# MainBoard_2020-05-08_18-35-21.net
KiCad netlist of a schematic drawn in EasyEDA
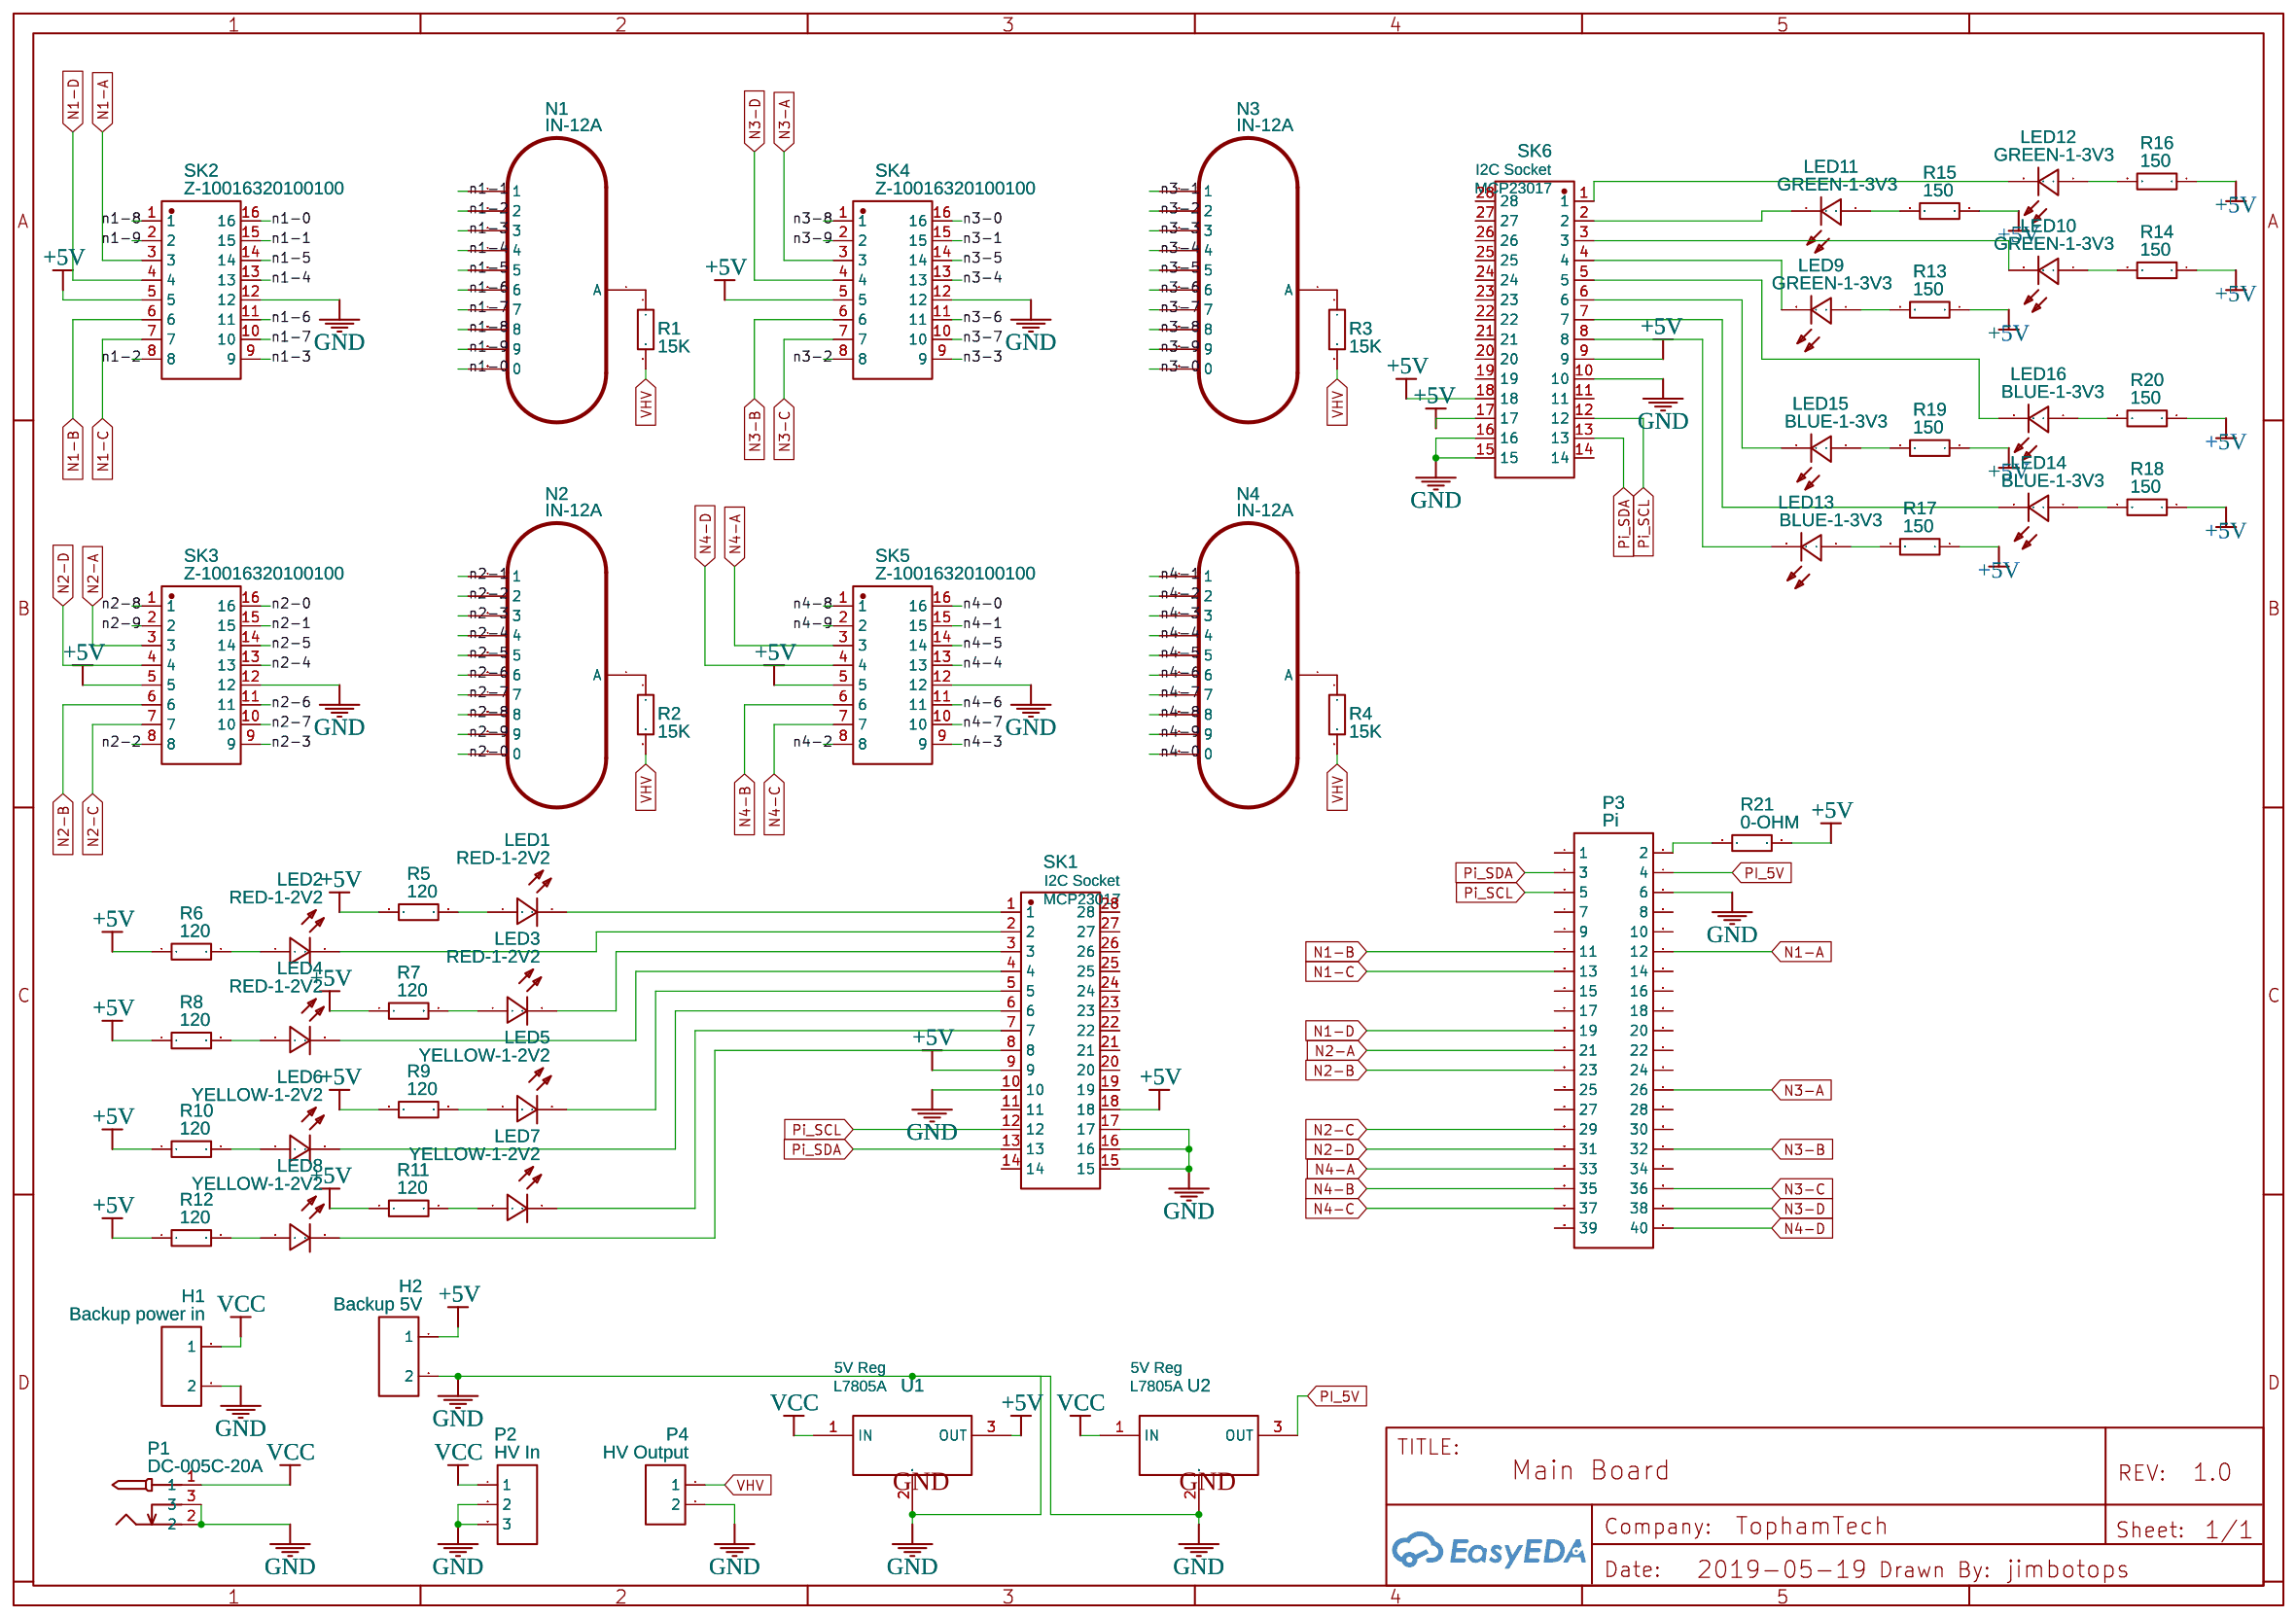
[diagram p0: schematic sheet]

(export (version "E")
  (design (tool "Eeschema 10.0.6"))
  (components
    (comp (ref "H1")
      (value "Backup power in")
      (fields (field (name "BOM_Manufacturer Part") "826629-2") (field (name "BOM_Supplier Part") "C86471"))
      (libsource (lib "") (part "Unknown_90_685"))
    )
    (comp (ref "H2")
      (value "Backup 5V")
      (fields (field (name "BOM_Manufacturer Part") "826629-2") (field (name "BOM_Supplier Part") "C86471"))
      (libsource (lib "") (part "Unknown_200_680"))
    )
    (comp (ref "LED1")
      (value "RED-1-2V2")
      (fields
        (field (name "BOM_Manufacturer Part") "11-21/GPC-AM2P1/2T")
        (field (name "BOM_Supplier Part") "C264329")
      )
      (libsource (lib "") (part "Unknown_260_455"))
    )
    (comp (ref "LED2")
      (value "RED-1-2V2")
      (fields
        (field (name "BOM_Manufacturer Part") "11-21/GPC-AM2P1/2T")
        (field (name "BOM_Supplier Part") "C264329")
      )
      (libsource (lib "") (part "Unknown_145_475"))
    )
    (comp (ref "LED3")
      (value "RED-1-2V2")
      (fields
        (field (name "BOM_Manufacturer Part") "11-21/GPC-AM2P1/2T")
        (field (name "BOM_Supplier Part") "C264329")
      )
      (libsource (lib "") (part "Unknown_255_505"))
    )
    (comp (ref "LED4")
      (value "RED-1-2V2")
      (fields
        (field (name "BOM_Manufacturer Part") "11-21/GPC-AM2P1/2T")
        (field (name "BOM_Supplier Part") "C264329")
      )
      (libsource (lib "") (part "Unknown_145_520"))
    )
    (comp (ref "LED5")
      (value "YELLOW-1-2V2")
      (fields
        (field (name "BOM_Manufacturer Part") "11-21/GPC-AM2P1/2T")
        (field (name "BOM_Supplier Part") "C264329")
      )
      (libsource (lib "") (part "Unknown_260_555"))
    )
    (comp (ref "LED6")
      (value "YELLOW-1-2V2")
      (fields
        (field (name "BOM_Manufacturer Part") "11-21/GPC-AM2P1/2T")
        (field (name "BOM_Supplier Part") "C264329")
      )
      (libsource (lib "") (part "Unknown_145_575"))
    )
    (comp (ref "LED7")
      (value "YELLOW-1-2V2")
      (fields
        (field (name "BOM_Manufacturer Part") "11-21/GPC-AM2P1/2T")
        (field (name "BOM_Supplier Part") "C264329")
      )
      (libsource (lib "") (part "Unknown_255_605"))
    )
    (comp (ref "LED8")
      (value "YELLOW-1-2V2")
      (fields
        (field (name "BOM_Manufacturer Part") "11-21/GPC-AM2P1/2T")
        (field (name "BOM_Supplier Part") "C264329")
      )
      (libsource (lib "") (part "Unknown_145_620"))
    )
    (comp (ref "LED9")
      (value "GREEN-1-3V3")
      (fields
        (field (name "BOM_Manufacturer Part") "11-21/GPC-AM2P1/2T")
        (field (name "BOM_Supplier Part") "C264329")
      )
      (libsource (lib "") (part "Unknown_915_150"))
    )
    (comp (ref "LED10")
      (value "GREEN-1-3V3")
      (fields
        (field (name "BOM_Manufacturer Part") "11-21/GPC-AM2P1/2T")
        (field (name "BOM_Supplier Part") "C264329")
      )
      (libsource (lib "") (part "Unknown_1030_130"))
    )
    (comp (ref "LED11")
      (value "GREEN-1-3V3")
      (fields
        (field (name "BOM_Manufacturer Part") "11-21/GPC-AM2P1/2T")
        (field (name "BOM_Supplier Part") "C264329")
      )
      (libsource (lib "") (part "Unknown_920_100"))
    )
    (comp (ref "LED12")
      (value "GREEN-1-3V3")
      (fields
        (field (name "BOM_Manufacturer Part") "11-21/GPC-AM2P1/2T")
        (field (name "BOM_Supplier Part") "C264329")
      )
      (libsource (lib "") (part "Unknown_1030_85"))
    )
    (comp (ref "LED13")
      (value "BLUE-1-3V3")
      (fields
        (field (name "BOM_Manufacturer Part") "11-21/GPC-AM2P1/2T")
        (field (name "BOM_Supplier Part") "C264329")
      )
      (libsource (lib "") (part "Unknown_910_270"))
    )
    (comp (ref "LED14")
      (value "BLUE-1-3V3")
      (fields
        (field (name "BOM_Manufacturer Part") "11-21/GPC-AM2P1/2T")
        (field (name "BOM_Supplier Part") "C264329")
      )
      (libsource (lib "") (part "Unknown_1025_250"))
    )
    (comp (ref "LED15")
      (value "BLUE-1-3V3")
      (fields
        (field (name "BOM_Manufacturer Part") "11-21/GPC-AM2P1/2T")
        (field (name "BOM_Supplier Part") "C264329")
      )
      (libsource (lib "") (part "Unknown_915_220"))
    )
    (comp (ref "LED16")
      (value "BLUE-1-3V3")
      (fields
        (field (name "BOM_Manufacturer Part") "11-21/GPC-AM2P1/2T")
        (field (name "BOM_Supplier Part") "C264329")
      )
      (libsource (lib "") (part "Unknown_1025_205"))
    )
    (comp (ref "N1")
      (value "IN-12A")
      (fields (field (name "BOM_Manufacturer Part") "?"))
      (libsource (lib "") (part "Unknown_275_135"))
    )
    (comp (ref "N2")
      (value "IN-12A")
      (fields (field (name "BOM_Manufacturer Part") "?"))
      (libsource (lib "") (part "Unknown_275_330"))
    )
    (comp (ref "N3")
      (value "IN-12A")
      (fields (field (name "BOM_Manufacturer Part") "?"))
      (libsource (lib "") (part "Unknown_625_135"))
    )
    (comp (ref "N4")
      (value "IN-12A")
      (fields (field (name "BOM_Manufacturer Part") "?"))
      (libsource (lib "") (part "Unknown_625_330"))
    )
    (comp (ref "P1")
      (value "DC-005C-20A")
      (fields (field (name "BOM_Supplier Part") "C84007"))
      (libsource (lib "") (part "Unknown_75_755"))
    )
    (comp (ref "P2")
      (value "HV In")
      (fields
        (field (name "BOM_Manufacturer Part") "Header-Female-2.54_1x3")
        (field (name "BOM_Supplier Part") "C146243")
      )
      (libsource (lib "") (part "Unknown_250_755"))
    )
    (comp (ref "P3")
      (value "Pi")
      (fields
        (field (name "BOM_Manufacturer Part") "2.54mm 2*20PFemale header")
        (field (name "BOM_Supplier Part") "C50982")
      )
      (libsource (lib "") (part "Unknown_810_525"))
    )
    (comp (ref "P4")
      (value "HV Output")
      (fields
        (field (name "BOM_Manufacturer Part") "2.54-1*2PFemale")
        (field (name "BOM_Supplier Part") "C49661")
      )
      (libsource (lib "") (part "Unknown_335_750"))
    )
    (comp (ref "R1")
      (value "15K")
      (fields
        (field (name "BOM_Manufacturer Part") "2010W2J0153T4S")
        (field (name "BOM_Supplier Part") "C20362")
      )
      (libsource (lib "") (part "2010W2J0153T4S"))
    )
    (comp (ref "R2")
      (value "15K")
      (fields
        (field (name "BOM_Manufacturer Part") "2010W2J0153T4S")
        (field (name "BOM_Supplier Part") "C20362")
      )
      (libsource (lib "") (part "2010W2J0153T4S"))
    )
    (comp (ref "R3")
      (value "15K")
      (fields
        (field (name "BOM_Manufacturer Part") "2010W2J0153T4S")
        (field (name "BOM_Supplier Part") "C20362")
      )
      (libsource (lib "") (part "2010W2J0153T4S"))
    )
    (comp (ref "R4")
      (value "15K")
      (fields
        (field (name "BOM_Manufacturer Part") "2010W2J0153T4S")
        (field (name "BOM_Supplier Part") "C20362")
      )
      (libsource (lib "") (part "2010W2J0153T4S"))
    )
    (comp (ref "R5")
      (value "120")
      (fields
        (field (name "BOM_Manufacturer Part") "1206W4F1200T5E")
        (field (name "BOM_Supplier Part") "C14661")
      )
      (libsource (lib "") (part "1206W4F1200T5E_1"))
    )
    (comp (ref "R6")
      (value "120")
      (fields
        (field (name "BOM_Manufacturer Part") "1206W4F1200T5E")
        (field (name "BOM_Supplier Part") "C14661")
      )
      (libsource (lib "") (part "1206W4F1200T5E_1"))
    )
    (comp (ref "R7")
      (value "120")
      (fields
        (field (name "BOM_Manufacturer Part") "1206W4F1200T5E")
        (field (name "BOM_Supplier Part") "C14661")
      )
      (libsource (lib "") (part "1206W4F1200T5E_1"))
    )
    (comp (ref "R8")
      (value "120")
      (fields
        (field (name "BOM_Manufacturer Part") "1206W4F1200T5E")
        (field (name "BOM_Supplier Part") "C14661")
      )
      (libsource (lib "") (part "1206W4F1200T5E_1"))
    )
    (comp (ref "R9")
      (value "120")
      (fields
        (field (name "BOM_Manufacturer Part") "1206W4F1200T5E")
        (field (name "BOM_Supplier Part") "C14661")
      )
      (libsource (lib "") (part "1206W4F1200T5E_1"))
    )
    (comp (ref "R10")
      (value "120")
      (fields
        (field (name "BOM_Manufacturer Part") "1206W4F1200T5E")
        (field (name "BOM_Supplier Part") "C14661")
      )
      (libsource (lib "") (part "1206W4F1200T5E_1"))
    )
    (comp (ref "R11")
      (value "120")
      (fields
        (field (name "BOM_Manufacturer Part") "1206W4F1200T5E")
        (field (name "BOM_Supplier Part") "C14661")
      )
      (libsource (lib "") (part "1206W4F1200T5E_1"))
    )
    (comp (ref "R12")
      (value "120")
      (fields
        (field (name "BOM_Manufacturer Part") "1206W4F1200T5E")
        (field (name "BOM_Supplier Part") "C14661")
      )
      (libsource (lib "") (part "1206W4F1200T5E_1"))
    )
    (comp (ref "R13")
      (value "150")
      (fields
        (field (name "BOM_Manufacturer Part") "1206W4F1200T5E")
        (field (name "BOM_Supplier Part") "C14661")
      )
      (libsource (lib "") (part "1206W4F1200T5E"))
    )
    (comp (ref "R14")
      (value "150")
      (fields
        (field (name "BOM_Manufacturer Part") "1206W4F1200T5E")
        (field (name "BOM_Supplier Part") "C14661")
      )
      (libsource (lib "") (part "1206W4F1200T5E"))
    )
    (comp (ref "R15")
      (value "150")
      (fields
        (field (name "BOM_Manufacturer Part") "1206W4F1200T5E")
        (field (name "BOM_Supplier Part") "C14661")
      )
      (libsource (lib "") (part "1206W4F1200T5E"))
    )
    (comp (ref "R16")
      (value "150")
      (fields
        (field (name "BOM_Manufacturer Part") "1206W4F1200T5E")
        (field (name "BOM_Supplier Part") "C14661")
      )
      (libsource (lib "") (part "1206W4F1200T5E"))
    )
    (comp (ref "R17")
      (value "150")
      (fields
        (field (name "BOM_Manufacturer Part") "1206W4F1200T5E")
        (field (name "BOM_Supplier Part") "C14661")
      )
      (libsource (lib "") (part "1206W4F1200T5E"))
    )
    (comp (ref "R18")
      (value "150")
      (fields
        (field (name "BOM_Manufacturer Part") "1206W4F1200T5E")
        (field (name "BOM_Supplier Part") "C14661")
      )
      (libsource (lib "") (part "1206W4F1200T5E"))
    )
    (comp (ref "R19")
      (value "150")
      (fields
        (field (name "BOM_Manufacturer Part") "1206W4F1200T5E")
        (field (name "BOM_Supplier Part") "C14661")
      )
      (libsource (lib "") (part "1206W4F1200T5E"))
    )
    (comp (ref "R20")
      (value "150")
      (fields
        (field (name "BOM_Manufacturer Part") "1206W4F1200T5E")
        (field (name "BOM_Supplier Part") "C14661")
      )
      (libsource (lib "") (part "1206W4F1200T5E"))
    )
    (comp (ref "R21")
      (value "0-OHM")
      (fields
        (field (name "BOM_Manufacturer Part") "1206W4F3650T5E")
        (field (name "BOM_Supplier Part") "C172882")
      )
      (libsource (lib "") (part "1206W4F3650T5E"))
    )
    (comp (ref "SK1")
      (value "I2C Socket\\nMCP23017")
      (fields (field (name "BOM_Supplier Part") "C146582"))
      (libsource (lib "") (part "Unknown_530_520"))
    )
    (comp (ref "SK2")
      (value "Z-10016320100100")
      (fields (field (name "BOM_Supplier Part") "C157594"))
      (libsource (lib "") (part "Unknown_95_140"))
    )
    (comp (ref "SK3")
      (value "Z-10016320100100")
      (fields (field (name "BOM_Supplier Part") "C157594"))
      (libsource (lib "") (part "Unknown_95_335"))
    )
    (comp (ref "SK4")
      (value "Z-10016320100100")
      (fields (field (name "BOM_Supplier Part") "C157594"))
      (libsource (lib "") (part "Unknown_445_140"))
    )
    (comp (ref "SK5")
      (value "Z-10016320100100")
      (fields (field (name "BOM_Supplier Part") "C157594"))
      (libsource (lib "") (part "Unknown_445_335"))
    )
    (comp (ref "SK6")
      (value "I2C Socket\\nMCP23017")
      (fields (field (name "BOM_Supplier Part") "C146582"))
      (libsource (lib "") (part "Unknown_770_160"))
    )
    (comp (ref "U1")
      (value "5V Reg\\nL7805A")
      (fields
        (field (name "BOM_Manufacturer Part") "L7805ABD2T-TR")
        (field (name "BOM_Supplier Part") "C86206")
      )
      (libsource (lib "") (part "Unknown_455_735"))
    )
    (comp (ref "U2")
      (value "5V Reg\\nL7805A")
      (fields
        (field (name "BOM_Manufacturer Part") "L7805ABD2T-TR")
        (field (name "BOM_Supplier Part") "C86206")
      )
      (libsource (lib "") (part "Unknown_600_735"))
    )
  )
  (nets
    (net (code "1") (name "+5V") (class "Default")
      (node (ref "H2") (pin "1") (pinfunction "1_1") (pintype "unspecified"))
      (node (ref "R10") (pin "1") (pinfunction "1_1") (pintype "input"))
      (node (ref "R11") (pin "1") (pinfunction "1_1") (pintype "input"))
      (node (ref "R12") (pin "1") (pinfunction "1_1") (pintype "input"))
      (node (ref "R13") (pin "1") (pinfunction "1_1") (pintype "input"))
      (node (ref "R14") (pin "1") (pinfunction "1_1") (pintype "input"))
      (node (ref "R15") (pin "1") (pinfunction "1_1") (pintype "input"))
      (node (ref "R16") (pin "1") (pinfunction "1_1") (pintype "input"))
      (node (ref "R17") (pin "1") (pinfunction "1_1") (pintype "input"))
      (node (ref "R18") (pin "1") (pinfunction "1_1") (pintype "input"))
      (node (ref "R19") (pin "1") (pinfunction "1_1") (pintype "input"))
      (node (ref "R20") (pin "1") (pinfunction "1_1") (pintype "input"))
      (node (ref "R21") (pin "2") (pinfunction "2_2") (pintype "unspecified"))
      (node (ref "R5") (pin "1") (pinfunction "1_1") (pintype "input"))
      (node (ref "R6") (pin "1") (pinfunction "1_1") (pintype "input"))
      (node (ref "R7") (pin "1") (pinfunction "1_1") (pintype "input"))
      (node (ref "R8") (pin "1") (pinfunction "1_1") (pintype "input"))
      (node (ref "R9") (pin "1") (pinfunction "1_1") (pintype "input"))
      (node (ref "SK1") (pin "18") (pinfunction "18_18") (pintype "unspecified"))
      (node (ref "SK1") (pin "9") (pinfunction "9_9") (pintype "unspecified"))
      (node (ref "SK2") (pin "5") (pinfunction "5_5") (pintype "unspecified"))
      (node (ref "SK3") (pin "5") (pinfunction "5_5") (pintype "unspecified"))
      (node (ref "SK4") (pin "5") (pinfunction "5_5") (pintype "unspecified"))
      (node (ref "SK5") (pin "5") (pinfunction "5_5") (pintype "unspecified"))
      (node (ref "SK6") (pin "17") (pinfunction "17_17") (pintype "unspecified"))
      (node (ref "SK6") (pin "18") (pinfunction "18_18") (pintype "unspecified"))
      (node (ref "SK6") (pin "9") (pinfunction "9_9") (pintype "unspecified"))
      (node (ref "U1") (pin "3") (pinfunction "OUT_3") (pintype "passive"))
    )
    (net (code "2") (name "/n1-0") (class "Default")
      (node (ref "N1") (pin "0") (pinfunction "0_0") (pintype "unspecified"))
      (node (ref "SK2") (pin "16") (pinfunction "16_16") (pintype "unspecified"))
    )
    (net (code "3") (name "/n1-1") (class "Default")
      (node (ref "N1") (pin "1") (pinfunction "1_1") (pintype "unspecified"))
      (node (ref "SK2") (pin "15") (pinfunction "15_15") (pintype "unspecified"))
    )
    (net (code "4") (name "/n1-2") (class "Default")
      (node (ref "N1") (pin "2") (pinfunction "2_2") (pintype "unspecified"))
      (node (ref "SK2") (pin "8") (pinfunction "8_8") (pintype "unspecified"))
    )
    (net (code "5") (name "/n1-3") (class "Default")
      (node (ref "N1") (pin "3") (pinfunction "3_3") (pintype "unspecified"))
      (node (ref "SK2") (pin "9") (pinfunction "9_9") (pintype "unspecified"))
    )
    (net (code "6") (name "/n1-4") (class "Default")
      (node (ref "N1") (pin "4") (pinfunction "4_4") (pintype "unspecified"))
      (node (ref "SK2") (pin "13") (pinfunction "13_13") (pintype "unspecified"))
    )
    (net (code "7") (name "/n1-5") (class "Default")
      (node (ref "N1") (pin "5") (pinfunction "5_5") (pintype "unspecified"))
      (node (ref "SK2") (pin "14") (pinfunction "14_14") (pintype "unspecified"))
    )
    (net (code "8") (name "/n1-6") (class "Default")
      (node (ref "N1") (pin "6") (pinfunction "6_6") (pintype "unspecified"))
      (node (ref "SK2") (pin "11") (pinfunction "11_11") (pintype "unspecified"))
    )
    (net (code "9") (name "/n1-7") (class "Default")
      (node (ref "N1") (pin "7") (pinfunction "7_7") (pintype "unspecified"))
      (node (ref "SK2") (pin "10") (pinfunction "10_10") (pintype "unspecified"))
    )
    (net (code "10") (name "/n1-8") (class "Default")
      (node (ref "N1") (pin "8") (pinfunction "8_8") (pintype "unspecified"))
      (node (ref "SK2") (pin "1") (pinfunction "1_1") (pintype "unspecified"))
    )
    (net (code "11") (name "/n1-9") (class "Default")
      (node (ref "N1") (pin "9") (pinfunction "9_9") (pintype "unspecified"))
      (node (ref "SK2") (pin "2") (pinfunction "2_2") (pintype "unspecified"))
    )
    (net (code "12") (name "/n2-0") (class "Default")
      (node (ref "N2") (pin "0") (pinfunction "0_0") (pintype "unspecified"))
      (node (ref "SK3") (pin "16") (pinfunction "16_16") (pintype "unspecified"))
    )
    (net (code "13") (name "/n2-1") (class "Default")
      (node (ref "N2") (pin "1") (pinfunction "1_1") (pintype "unspecified"))
      (node (ref "SK3") (pin "15") (pinfunction "15_15") (pintype "unspecified"))
    )
    (net (code "14") (name "/n2-2") (class "Default")
      (node (ref "N2") (pin "2") (pinfunction "2_2") (pintype "unspecified"))
      (node (ref "SK3") (pin "8") (pinfunction "8_8") (pintype "unspecified"))
    )
    (net (code "15") (name "/n2-3") (class "Default")
      (node (ref "N2") (pin "3") (pinfunction "3_3") (pintype "unspecified"))
      (node (ref "SK3") (pin "9") (pinfunction "9_9") (pintype "unspecified"))
    )
    (net (code "16") (name "/n2-4") (class "Default")
      (node (ref "N2") (pin "4") (pinfunction "4_4") (pintype "unspecified"))
      (node (ref "SK3") (pin "13") (pinfunction "13_13") (pintype "unspecified"))
    )
    (net (code "17") (name "/n2-5") (class "Default")
      (node (ref "N2") (pin "5") (pinfunction "5_5") (pintype "unspecified"))
      (node (ref "SK3") (pin "14") (pinfunction "14_14") (pintype "unspecified"))
    )
    (net (code "18") (name "/n2-6") (class "Default")
      (node (ref "N2") (pin "6") (pinfunction "6_6") (pintype "unspecified"))
      (node (ref "SK3") (pin "11") (pinfunction "11_11") (pintype "unspecified"))
    )
    (net (code "19") (name "/n2-7") (class "Default")
      (node (ref "N2") (pin "7") (pinfunction "7_7") (pintype "unspecified"))
      (node (ref "SK3") (pin "10") (pinfunction "10_10") (pintype "unspecified"))
    )
    (net (code "20") (name "/n2-8") (class "Default")
      (node (ref "N2") (pin "8") (pinfunction "8_8") (pintype "unspecified"))
      (node (ref "SK3") (pin "1") (pinfunction "1_1") (pintype "unspecified"))
    )
    (net (code "21") (name "/n2-9") (class "Default")
      (node (ref "N2") (pin "9") (pinfunction "9_9") (pintype "unspecified"))
      (node (ref "SK3") (pin "2") (pinfunction "2_2") (pintype "unspecified"))
    )
    (net (code "22") (name "/n3-0") (class "Default")
      (node (ref "N3") (pin "0") (pinfunction "0_0") (pintype "unspecified"))
      (node (ref "SK4") (pin "16") (pinfunction "16_16") (pintype "unspecified"))
    )
    (net (code "23") (name "/n3-1") (class "Default")
      (node (ref "N3") (pin "1") (pinfunction "1_1") (pintype "unspecified"))
      (node (ref "SK4") (pin "15") (pinfunction "15_15") (pintype "unspecified"))
    )
    (net (code "24") (name "/n3-2") (class "Default")
      (node (ref "N3") (pin "2") (pinfunction "2_2") (pintype "unspecified"))
      (node (ref "SK4") (pin "8") (pinfunction "8_8") (pintype "unspecified"))
    )
    (net (code "25") (name "/n3-3") (class "Default")
      (node (ref "N3") (pin "3") (pinfunction "3_3") (pintype "unspecified"))
      (node (ref "SK4") (pin "9") (pinfunction "9_9") (pintype "unspecified"))
    )
    (net (code "26") (name "/n3-4") (class "Default")
      (node (ref "N3") (pin "4") (pinfunction "4_4") (pintype "unspecified"))
      (node (ref "SK4") (pin "13") (pinfunction "13_13") (pintype "unspecified"))
    )
    (net (code "27") (name "/n3-5") (class "Default")
      (node (ref "N3") (pin "5") (pinfunction "5_5") (pintype "unspecified"))
      (node (ref "SK4") (pin "14") (pinfunction "14_14") (pintype "unspecified"))
    )
    (net (code "28") (name "/n3-6") (class "Default")
      (node (ref "N3") (pin "6") (pinfunction "6_6") (pintype "unspecified"))
      (node (ref "SK4") (pin "11") (pinfunction "11_11") (pintype "unspecified"))
    )
    (net (code "29") (name "/n3-7") (class "Default")
      (node (ref "N3") (pin "7") (pinfunction "7_7") (pintype "unspecified"))
      (node (ref "SK4") (pin "10") (pinfunction "10_10") (pintype "unspecified"))
    )
    (net (code "30") (name "/n3-8") (class "Default")
      (node (ref "N3") (pin "8") (pinfunction "8_8") (pintype "unspecified"))
      (node (ref "SK4") (pin "1") (pinfunction "1_1") (pintype "unspecified"))
    )
    (net (code "31") (name "/n3-9") (class "Default")
      (node (ref "N3") (pin "9") (pinfunction "9_9") (pintype "unspecified"))
      (node (ref "SK4") (pin "2") (pinfunction "2_2") (pintype "unspecified"))
    )
    (net (code "32") (name "/n4-0") (class "Default")
      (node (ref "N4") (pin "0") (pinfunction "0_0") (pintype "unspecified"))
      (node (ref "SK5") (pin "16") (pinfunction "16_16") (pintype "unspecified"))
    )
    (net (code "33") (name "/n4-1") (class "Default")
      (node (ref "N4") (pin "1") (pinfunction "1_1") (pintype "unspecified"))
      (node (ref "SK5") (pin "15") (pinfunction "15_15") (pintype "unspecified"))
    )
    (net (code "34") (name "/n4-2") (class "Default")
      (node (ref "N4") (pin "2") (pinfunction "2_2") (pintype "unspecified"))
      (node (ref "SK5") (pin "8") (pinfunction "8_8") (pintype "unspecified"))
    )
    (net (code "35") (name "/n4-3") (class "Default")
      (node (ref "N4") (pin "3") (pinfunction "3_3") (pintype "unspecified"))
      (node (ref "SK5") (pin "9") (pinfunction "9_9") (pintype "unspecified"))
    )
    (net (code "36") (name "/n4-4") (class "Default")
      (node (ref "N4") (pin "4") (pinfunction "4_4") (pintype "unspecified"))
      (node (ref "SK5") (pin "13") (pinfunction "13_13") (pintype "unspecified"))
    )
    (net (code "37") (name "/n4-5") (class "Default")
      (node (ref "N4") (pin "5") (pinfunction "5_5") (pintype "unspecified"))
      (node (ref "SK5") (pin "14") (pinfunction "14_14") (pintype "unspecified"))
    )
    (net (code "38") (name "/n4-6") (class "Default")
      (node (ref "N4") (pin "6") (pinfunction "6_6") (pintype "unspecified"))
      (node (ref "SK5") (pin "11") (pinfunction "11_11") (pintype "unspecified"))
    )
    (net (code "39") (name "/n4-7") (class "Default")
      (node (ref "N4") (pin "7") (pinfunction "7_7") (pintype "unspecified"))
      (node (ref "SK5") (pin "10") (pinfunction "10_10") (pintype "unspecified"))
    )
    (net (code "40") (name "/n4-8") (class "Default")
      (node (ref "N4") (pin "8") (pinfunction "8_8") (pintype "unspecified"))
      (node (ref "SK5") (pin "1") (pinfunction "1_1") (pintype "unspecified"))
    )
    (net (code "41") (name "/n4-9") (class "Default")
      (node (ref "N4") (pin "9") (pinfunction "9_9") (pintype "unspecified"))
      (node (ref "SK5") (pin "2") (pinfunction "2_2") (pintype "unspecified"))
    )
    (net (code "42") (name "GND") (class "Default")
      (node (ref "H1") (pin "2") (pinfunction "2_2") (pintype "unspecified"))
      (node (ref "H2") (pin "2") (pinfunction "2_2") (pintype "unspecified"))
      (node (ref "P1") (pin "2") (pinfunction "2_2") (pintype "unspecified"))
      (node (ref "P1") (pin "3") (pinfunction "3_3") (pintype "unspecified"))
      (node (ref "P2") (pin "2") (pinfunction "2_2") (pintype "input"))
      (node (ref "P2") (pin "3") (pinfunction "3_3") (pintype "input"))
      (node (ref "P3") (pin "6") (pinfunction "6_6") (pintype "input"))
      (node (ref "P4") (pin "2") (pinfunction "2_2") (pintype "input"))
      (node (ref "SK1") (pin "10") (pinfunction "10_10") (pintype "unspecified"))
      (node (ref "SK1") (pin "15") (pinfunction "15_15") (pintype "unspecified"))
      (node (ref "SK1") (pin "16") (pinfunction "16_16") (pintype "unspecified"))
      (node (ref "SK1") (pin "17") (pinfunction "17_17") (pintype "unspecified"))
      (node (ref "SK2") (pin "12") (pinfunction "12_12") (pintype "unspecified"))
      (node (ref "SK3") (pin "12") (pinfunction "12_12") (pintype "unspecified"))
      (node (ref "SK4") (pin "12") (pinfunction "12_12") (pintype "unspecified"))
      (node (ref "SK5") (pin "12") (pinfunction "12_12") (pintype "unspecified"))
      (node (ref "SK6") (pin "10") (pinfunction "10_10") (pintype "unspecified"))
      (node (ref "SK6") (pin "15") (pinfunction "15_15") (pintype "unspecified"))
      (node (ref "SK6") (pin "16") (pinfunction "16_16") (pintype "unspecified"))
      (node (ref "U1") (pin "2") (pinfunction "GND_2") (pintype "passive"))
      (node (ref "U2") (pin "2") (pinfunction "GND_2") (pintype "passive"))
    )
    (net (code "43") (name "N1-A") (class "Default")
      (node (ref "P3") (pin "12") (pinfunction "12_12") (pintype "input"))
      (node (ref "SK2") (pin "3") (pinfunction "3_3") (pintype "unspecified"))
    )
    (net (code "44") (name "N1-B") (class "Default")
      (node (ref "P3") (pin "11") (pinfunction "11_11") (pintype "input"))
      (node (ref "SK2") (pin "6") (pinfunction "6_6") (pintype "unspecified"))
    )
    (net (code "45") (name "N1-C") (class "Default")
      (node (ref "P3") (pin "13") (pinfunction "13_13") (pintype "input"))
      (node (ref "SK2") (pin "7") (pinfunction "7_7") (pintype "unspecified"))
    )
    (net (code "46") (name "N1-D") (class "Default")
      (node (ref "P3") (pin "19") (pinfunction "19_19") (pintype "input"))
      (node (ref "SK2") (pin "4") (pinfunction "4_4") (pintype "unspecified"))
    )
    (net (code "47") (name "N2-A") (class "Default")
      (node (ref "P3") (pin "21") (pinfunction "21_21") (pintype "input"))
      (node (ref "SK3") (pin "3") (pinfunction "3_3") (pintype "unspecified"))
    )
    (net (code "48") (name "N2-B") (class "Default")
      (node (ref "P3") (pin "23") (pinfunction "23_23") (pintype "input"))
      (node (ref "SK3") (pin "6") (pinfunction "6_6") (pintype "unspecified"))
    )
    (net (code "49") (name "N2-C") (class "Default")
      (node (ref "P3") (pin "29") (pinfunction "29_29") (pintype "input"))
      (node (ref "SK3") (pin "7") (pinfunction "7_7") (pintype "unspecified"))
    )
    (net (code "50") (name "N2-D") (class "Default")
      (node (ref "P3") (pin "31") (pinfunction "31_31") (pintype "input"))
      (node (ref "SK3") (pin "4") (pinfunction "4_4") (pintype "unspecified"))
    )
    (net (code "51") (name "N3-A") (class "Default")
      (node (ref "P3") (pin "26") (pinfunction "26_26") (pintype "input"))
      (node (ref "SK4") (pin "3") (pinfunction "3_3") (pintype "unspecified"))
    )
    (net (code "52") (name "N3-B") (class "Default")
      (node (ref "P3") (pin "32") (pinfunction "32_32") (pintype "input"))
      (node (ref "SK4") (pin "6") (pinfunction "6_6") (pintype "unspecified"))
    )
    (net (code "53") (name "N3-C") (class "Default")
      (node (ref "P3") (pin "36") (pinfunction "36_36") (pintype "input"))
      (node (ref "SK4") (pin "7") (pinfunction "7_7") (pintype "unspecified"))
    )
    (net (code "54") (name "N3-D") (class "Default")
      (node (ref "P3") (pin "38") (pinfunction "38_38") (pintype "input"))
      (node (ref "SK4") (pin "4") (pinfunction "4_4") (pintype "unspecified"))
    )
    (net (code "55") (name "N4-A") (class "Default")
      (node (ref "P3") (pin "33") (pinfunction "33_33") (pintype "input"))
      (node (ref "SK5") (pin "3") (pinfunction "3_3") (pintype "unspecified"))
    )
    (net (code "56") (name "N4-B") (class "Default")
      (node (ref "P3") (pin "35") (pinfunction "35_35") (pintype "input"))
      (node (ref "SK5") (pin "6") (pinfunction "6_6") (pintype "unspecified"))
    )
    (net (code "57") (name "N4-C") (class "Default")
      (node (ref "P3") (pin "37") (pinfunction "37_37") (pintype "input"))
      (node (ref "SK5") (pin "7") (pinfunction "7_7") (pintype "unspecified"))
    )
    (net (code "58") (name "N4-D") (class "Default")
      (node (ref "P3") (pin "40") (pinfunction "40_40") (pintype "input"))
      (node (ref "SK5") (pin "4") (pinfunction "4_4") (pintype "unspecified"))
    )
    (net (code "59") (name "Net-(LED1-A)") (class "Default")
      (node (ref "LED1") (pin "1") (pinfunction "A_1") (pintype "unspecified"))
      (node (ref "R5") (pin "2") (pinfunction "2_2") (pintype "input"))
    )
    (net (code "60") (name "Net-(LED1-K)") (class "Default")
      (node (ref "LED1") (pin "2") (pinfunction "K_2") (pintype "unspecified"))
      (node (ref "SK1") (pin "1") (pinfunction "1_1") (pintype "unspecified"))
    )
    (net (code "61") (name "Net-(LED2-A)") (class "Default")
      (node (ref "LED2") (pin "1") (pinfunction "A_1") (pintype "unspecified"))
      (node (ref "R6") (pin "2") (pinfunction "2_2") (pintype "input"))
    )
    (net (code "62") (name "Net-(LED2-K)") (class "Default")
      (node (ref "LED2") (pin "2") (pinfunction "K_2") (pintype "unspecified"))
      (node (ref "SK1") (pin "2") (pinfunction "2_2") (pintype "unspecified"))
    )
    (net (code "63") (name "Net-(LED3-A)") (class "Default")
      (node (ref "LED3") (pin "1") (pinfunction "A_1") (pintype "unspecified"))
      (node (ref "R7") (pin "2") (pinfunction "2_2") (pintype "input"))
    )
    (net (code "64") (name "Net-(LED3-K)") (class "Default")
      (node (ref "LED3") (pin "2") (pinfunction "K_2") (pintype "unspecified"))
      (node (ref "SK1") (pin "3") (pinfunction "3_3") (pintype "unspecified"))
    )
    (net (code "65") (name "Net-(LED4-A)") (class "Default")
      (node (ref "LED4") (pin "1") (pinfunction "A_1") (pintype "unspecified"))
      (node (ref "R8") (pin "2") (pinfunction "2_2") (pintype "input"))
    )
    (net (code "66") (name "Net-(LED4-K)") (class "Default")
      (node (ref "LED4") (pin "2") (pinfunction "K_2") (pintype "unspecified"))
      (node (ref "SK1") (pin "4") (pinfunction "4_4") (pintype "unspecified"))
    )
    (net (code "67") (name "Net-(LED5-A)") (class "Default")
      (node (ref "LED5") (pin "1") (pinfunction "A_1") (pintype "unspecified"))
      (node (ref "R9") (pin "2") (pinfunction "2_2") (pintype "input"))
    )
    (net (code "68") (name "Net-(LED5-K)") (class "Default")
      (node (ref "LED5") (pin "2") (pinfunction "K_2") (pintype "unspecified"))
      (node (ref "SK1") (pin "5") (pinfunction "5_5") (pintype "unspecified"))
    )
    (net (code "69") (name "Net-(LED6-A)") (class "Default")
      (node (ref "LED6") (pin "1") (pinfunction "A_1") (pintype "unspecified"))
      (node (ref "R10") (pin "2") (pinfunction "2_2") (pintype "input"))
    )
    (net (code "70") (name "Net-(LED6-K)") (class "Default")
      (node (ref "LED6") (pin "2") (pinfunction "K_2") (pintype "unspecified"))
      (node (ref "SK1") (pin "6") (pinfunction "6_6") (pintype "unspecified"))
    )
    (net (code "71") (name "Net-(LED7-A)") (class "Default")
      (node (ref "LED7") (pin "1") (pinfunction "A_1") (pintype "unspecified"))
      (node (ref "R11") (pin "2") (pinfunction "2_2") (pintype "input"))
    )
    (net (code "72") (name "Net-(LED7-K)") (class "Default")
      (node (ref "LED7") (pin "2") (pinfunction "K_2") (pintype "unspecified"))
      (node (ref "SK1") (pin "7") (pinfunction "7_7") (pintype "unspecified"))
    )
    (net (code "73") (name "Net-(LED8-A)") (class "Default")
      (node (ref "LED8") (pin "1") (pinfunction "A_1") (pintype "unspecified"))
      (node (ref "R12") (pin "2") (pinfunction "2_2") (pintype "input"))
    )
    (net (code "74") (name "Net-(LED8-K)") (class "Default")
      (node (ref "LED8") (pin "2") (pinfunction "K_2") (pintype "unspecified"))
      (node (ref "SK1") (pin "8") (pinfunction "8_8") (pintype "unspecified"))
    )
    (net (code "75") (name "Net-(LED9-A)") (class "Default")
      (node (ref "LED9") (pin "1") (pinfunction "A_1") (pintype "unspecified"))
      (node (ref "R13") (pin "2") (pinfunction "2_2") (pintype "input"))
    )
    (net (code "76") (name "Net-(LED9-K)") (class "Default")
      (node (ref "LED9") (pin "2") (pinfunction "K_2") (pintype "unspecified"))
      (node (ref "SK6") (pin "4") (pinfunction "4_4") (pintype "unspecified"))
    )
    (net (code "77") (name "Net-(LED10-A)") (class "Default")
      (node (ref "LED10") (pin "1") (pinfunction "A_1") (pintype "unspecified"))
      (node (ref "R14") (pin "2") (pinfunction "2_2") (pintype "input"))
    )
    (net (code "78") (name "Net-(LED10-K)") (class "Default")
      (node (ref "LED10") (pin "2") (pinfunction "K_2") (pintype "unspecified"))
      (node (ref "SK6") (pin "3") (pinfunction "3_3") (pintype "unspecified"))
    )
    (net (code "79") (name "Net-(LED11-A)") (class "Default")
      (node (ref "LED11") (pin "1") (pinfunction "A_1") (pintype "unspecified"))
      (node (ref "R15") (pin "2") (pinfunction "2_2") (pintype "input"))
    )
    (net (code "80") (name "Net-(LED11-K)") (class "Default")
      (node (ref "LED11") (pin "2") (pinfunction "K_2") (pintype "unspecified"))
      (node (ref "SK6") (pin "2") (pinfunction "2_2") (pintype "unspecified"))
    )
    (net (code "81") (name "Net-(LED12-A)") (class "Default")
      (node (ref "LED12") (pin "1") (pinfunction "A_1") (pintype "unspecified"))
      (node (ref "R16") (pin "2") (pinfunction "2_2") (pintype "input"))
    )
    (net (code "82") (name "Net-(LED12-K)") (class "Default")
      (node (ref "LED12") (pin "2") (pinfunction "K_2") (pintype "unspecified"))
      (node (ref "SK6") (pin "1") (pinfunction "1_1") (pintype "unspecified"))
    )
    (net (code "83") (name "Net-(LED13-A)") (class "Default")
      (node (ref "LED13") (pin "1") (pinfunction "A_1") (pintype "unspecified"))
      (node (ref "R17") (pin "2") (pinfunction "2_2") (pintype "input"))
    )
    (net (code "84") (name "Net-(LED13-K)") (class "Default")
      (node (ref "LED13") (pin "2") (pinfunction "K_2") (pintype "unspecified"))
      (node (ref "SK6") (pin "8") (pinfunction "8_8") (pintype "unspecified"))
    )
    (net (code "85") (name "Net-(LED14-A)") (class "Default")
      (node (ref "LED14") (pin "1") (pinfunction "A_1") (pintype "unspecified"))
      (node (ref "R18") (pin "2") (pinfunction "2_2") (pintype "input"))
    )
    (net (code "86") (name "Net-(LED14-K)") (class "Default")
      (node (ref "LED14") (pin "2") (pinfunction "K_2") (pintype "unspecified"))
      (node (ref "SK6") (pin "7") (pinfunction "7_7") (pintype "unspecified"))
    )
    (net (code "87") (name "Net-(LED15-A)") (class "Default")
      (node (ref "LED15") (pin "1") (pinfunction "A_1") (pintype "unspecified"))
      (node (ref "R19") (pin "2") (pinfunction "2_2") (pintype "input"))
    )
    (net (code "88") (name "Net-(LED15-K)") (class "Default")
      (node (ref "LED15") (pin "2") (pinfunction "K_2") (pintype "unspecified"))
      (node (ref "SK6") (pin "6") (pinfunction "6_6") (pintype "unspecified"))
    )
    (net (code "89") (name "Net-(LED16-A)") (class "Default")
      (node (ref "LED16") (pin "1") (pinfunction "A_1") (pintype "unspecified"))
      (node (ref "R20") (pin "2") (pinfunction "2_2") (pintype "input"))
    )
    (net (code "90") (name "Net-(LED16-K)") (class "Default")
      (node (ref "LED16") (pin "2") (pinfunction "K_2") (pintype "unspecified"))
      (node (ref "SK6") (pin "5") (pinfunction "5_5") (pintype "unspecified"))
    )
    (net (code "91") (name "Net-(N1-PadA)") (class "Default")
      (node (ref "N1") (pin "A") (pinfunction "A_A") (pintype "unspecified"))
      (node (ref "R1") (pin "1") (pinfunction "1_1") (pintype "input"))
    )
    (net (code "92") (name "Net-(N2-PadA)") (class "Default")
      (node (ref "N2") (pin "A") (pinfunction "A_A") (pintype "unspecified"))
      (node (ref "R2") (pin "1") (pinfunction "1_1") (pintype "input"))
    )
    (net (code "93") (name "Net-(N3-PadA)") (class "Default")
      (node (ref "N3") (pin "A") (pinfunction "A_A") (pintype "unspecified"))
      (node (ref "R3") (pin "1") (pinfunction "1_1") (pintype "input"))
    )
    (net (code "94") (name "Net-(N4-PadA)") (class "Default")
      (node (ref "N4") (pin "A") (pinfunction "A_A") (pintype "unspecified"))
      (node (ref "R4") (pin "1") (pinfunction "1_1") (pintype "input"))
    )
    (net (code "95") (name "Net-(P3-Pad2)") (class "Default")
      (node (ref "P3") (pin "2") (pinfunction "2_2") (pintype "input"))
      (node (ref "R21") (pin "1") (pinfunction "1_1") (pintype "unspecified"))
    )
    (net (code "96") (name "PI_5V") (class "Default")
      (node (ref "P3") (pin "4") (pinfunction "4_4") (pintype "input"))
      (node (ref "U2") (pin "3") (pinfunction "OUT_3") (pintype "passive"))
    )
    (net (code "97") (name "Pi_SCL") (class "Default")
      (node (ref "P3") (pin "5") (pinfunction "5_5") (pintype "input"))
      (node (ref "SK1") (pin "12") (pinfunction "12_12") (pintype "unspecified"))
      (node (ref "SK6") (pin "12") (pinfunction "12_12") (pintype "unspecified"))
    )
    (net (code "98") (name "Pi_SDA") (class "Default")
      (node (ref "P3") (pin "3") (pinfunction "3_3") (pintype "input"))
      (node (ref "SK1") (pin "13") (pinfunction "13_13") (pintype "unspecified"))
      (node (ref "SK6") (pin "13") (pinfunction "13_13") (pintype "unspecified"))
    )
    (net (code "99") (name "VCC") (class "Default")
      (node (ref "H1") (pin "1") (pinfunction "1_1") (pintype "unspecified"))
      (node (ref "P1") (pin "1") (pinfunction "1_1") (pintype "unspecified"))
      (node (ref "P2") (pin "1") (pinfunction "1_1") (pintype "input"))
      (node (ref "U1") (pin "1") (pinfunction "IN_1") (pintype "passive"))
      (node (ref "U2") (pin "1") (pinfunction "IN_1") (pintype "passive"))
    )
    (net (code "100") (name "VHV") (class "Default")
      (node (ref "P4") (pin "1") (pinfunction "1_1") (pintype "input"))
      (node (ref "R1") (pin "2") (pinfunction "2_2") (pintype "input"))
      (node (ref "R2") (pin "2") (pinfunction "2_2") (pintype "input"))
      (node (ref "R3") (pin "2") (pinfunction "2_2") (pintype "input"))
      (node (ref "R4") (pin "2") (pinfunction "2_2") (pintype "input"))
    )
    (net (code "101") (name "unconnected-(P3-Pad1)") (class "Default")
      (node (ref "P3") (pin "1") (pinfunction "1_1") (pintype "input"))
    )
    (net (code "102") (name "unconnected-(P3-Pad7)") (class "Default")
      (node (ref "P3") (pin "7") (pinfunction "7_7") (pintype "input"))
    )
    (net (code "103") (name "unconnected-(P3-Pad8)") (class "Default")
      (node (ref "P3") (pin "8") (pinfunction "8_8") (pintype "input"))
    )
    (net (code "104") (name "unconnected-(P3-Pad9)") (class "Default")
      (node (ref "P3") (pin "9") (pinfunction "9_9") (pintype "input"))
    )
    (net (code "105") (name "unconnected-(P3-Pad10)") (class "Default")
      (node (ref "P3") (pin "10") (pinfunction "10_10") (pintype "input"))
    )
    (net (code "106") (name "unconnected-(P3-Pad14)") (class "Default")
      (node (ref "P3") (pin "14") (pinfunction "14_14") (pintype "input"))
    )
    (net (code "107") (name "unconnected-(P3-Pad15)") (class "Default")
      (node (ref "P3") (pin "15") (pinfunction "15_15") (pintype "input"))
    )
    (net (code "108") (name "unconnected-(P3-Pad16)") (class "Default")
      (node (ref "P3") (pin "16") (pinfunction "16_16") (pintype "input"))
    )
    (net (code "109") (name "unconnected-(P3-Pad17)") (class "Default")
      (node (ref "P3") (pin "17") (pinfunction "17_17") (pintype "input"))
    )
    (net (code "110") (name "unconnected-(P3-Pad18)") (class "Default")
      (node (ref "P3") (pin "18") (pinfunction "18_18") (pintype "input"))
    )
    (net (code "111") (name "unconnected-(P3-Pad20)") (class "Default")
      (node (ref "P3") (pin "20") (pinfunction "20_20") (pintype "input"))
    )
    (net (code "112") (name "unconnected-(P3-Pad22)") (class "Default")
      (node (ref "P3") (pin "22") (pinfunction "22_22") (pintype "input"))
    )
    (net (code "113") (name "unconnected-(P3-Pad24)") (class "Default")
      (node (ref "P3") (pin "24") (pinfunction "24_24") (pintype "input"))
    )
    (net (code "114") (name "unconnected-(P3-Pad25)") (class "Default")
      (node (ref "P3") (pin "25") (pinfunction "25_25") (pintype "input"))
    )
    (net (code "115") (name "unconnected-(P3-Pad27)") (class "Default")
      (node (ref "P3") (pin "27") (pinfunction "27_27") (pintype "input"))
    )
    (net (code "116") (name "unconnected-(P3-Pad28)") (class "Default")
      (node (ref "P3") (pin "28") (pinfunction "28_28") (pintype "input"))
    )
    (net (code "117") (name "unconnected-(P3-Pad30)") (class "Default")
      (node (ref "P3") (pin "30") (pinfunction "30_30") (pintype "input"))
    )
    (net (code "118") (name "unconnected-(P3-Pad34)") (class "Default")
      (node (ref "P3") (pin "34") (pinfunction "34_34") (pintype "input"))
    )
    (net (code "119") (name "unconnected-(P3-Pad39)") (class "Default")
      (node (ref "P3") (pin "39") (pinfunction "39_39") (pintype "input"))
    )
    (net (code "120") (name "unconnected-(SK1-Pad11)") (class "Default")
      (node (ref "SK1") (pin "11") (pinfunction "11_11") (pintype "unspecified"))
    )
    (net (code "121") (name "unconnected-(SK1-Pad14)") (class "Default")
      (node (ref "SK1") (pin "14") (pinfunction "14_14") (pintype "unspecified"))
    )
    (net (code "122") (name "unconnected-(SK1-Pad19)") (class "Default")
      (node (ref "SK1") (pin "19") (pinfunction "19_19") (pintype "unspecified"))
    )
    (net (code "123") (name "unconnected-(SK1-Pad20)") (class "Default")
      (node (ref "SK1") (pin "20") (pinfunction "20_20") (pintype "unspecified"))
    )
    (net (code "124") (name "unconnected-(SK1-Pad21)") (class "Default")
      (node (ref "SK1") (pin "21") (pinfunction "21_21") (pintype "unspecified"))
    )
    (net (code "125") (name "unconnected-(SK1-Pad22)") (class "Default")
      (node (ref "SK1") (pin "22") (pinfunction "22_22") (pintype "unspecified"))
    )
    (net (code "126") (name "unconnected-(SK1-Pad23)") (class "Default")
      (node (ref "SK1") (pin "23") (pinfunction "23_23") (pintype "unspecified"))
    )
    (net (code "127") (name "unconnected-(SK1-Pad24)") (class "Default")
      (node (ref "SK1") (pin "24") (pinfunction "24_24") (pintype "unspecified"))
    )
    (net (code "128") (name "unconnected-(SK1-Pad25)") (class "Default")
      (node (ref "SK1") (pin "25") (pinfunction "25_25") (pintype "unspecified"))
    )
    (net (code "129") (name "unconnected-(SK1-Pad26)") (class "Default")
      (node (ref "SK1") (pin "26") (pinfunction "26_26") (pintype "unspecified"))
    )
    (net (code "130") (name "unconnected-(SK1-Pad27)") (class "Default")
      (node (ref "SK1") (pin "27") (pinfunction "27_27") (pintype "unspecified"))
    )
    (net (code "131") (name "unconnected-(SK1-Pad28)") (class "Default")
      (node (ref "SK1") (pin "28") (pinfunction "28_28") (pintype "unspecified"))
    )
    (net (code "132") (name "unconnected-(SK6-Pad11)") (class "Default")
      (node (ref "SK6") (pin "11") (pinfunction "11_11") (pintype "unspecified"))
    )
    (net (code "133") (name "unconnected-(SK6-Pad14)") (class "Default")
      (node (ref "SK6") (pin "14") (pinfunction "14_14") (pintype "unspecified"))
    )
    (net (code "134") (name "unconnected-(SK6-Pad19)") (class "Default")
      (node (ref "SK6") (pin "19") (pinfunction "19_19") (pintype "unspecified"))
    )
    (net (code "135") (name "unconnected-(SK6-Pad20)") (class "Default")
      (node (ref "SK6") (pin "20") (pinfunction "20_20") (pintype "unspecified"))
    )
    (net (code "136") (name "unconnected-(SK6-Pad21)") (class "Default")
      (node (ref "SK6") (pin "21") (pinfunction "21_21") (pintype "unspecified"))
    )
    (net (code "137") (name "unconnected-(SK6-Pad22)") (class "Default")
      (node (ref "SK6") (pin "22") (pinfunction "22_22") (pintype "unspecified"))
    )
    (net (code "138") (name "unconnected-(SK6-Pad23)") (class "Default")
      (node (ref "SK6") (pin "23") (pinfunction "23_23") (pintype "unspecified"))
    )
    (net (code "139") (name "unconnected-(SK6-Pad24)") (class "Default")
      (node (ref "SK6") (pin "24") (pinfunction "24_24") (pintype "unspecified"))
    )
    (net (code "140") (name "unconnected-(SK6-Pad25)") (class "Default")
      (node (ref "SK6") (pin "25") (pinfunction "25_25") (pintype "unspecified"))
    )
    (net (code "141") (name "unconnected-(SK6-Pad26)") (class "Default")
      (node (ref "SK6") (pin "26") (pinfunction "26_26") (pintype "unspecified"))
    )
    (net (code "142") (name "unconnected-(SK6-Pad27)") (class "Default")
      (node (ref "SK6") (pin "27") (pinfunction "27_27") (pintype "unspecified"))
    )
    (net (code "143") (name "unconnected-(SK6-Pad28)") (class "Default")
      (node (ref "SK6") (pin "28") (pinfunction "28_28") (pintype "unspecified"))
    )
  )
)
